# PDB_design.net
KiCad netlist of a schematic drawn in Altium Designer
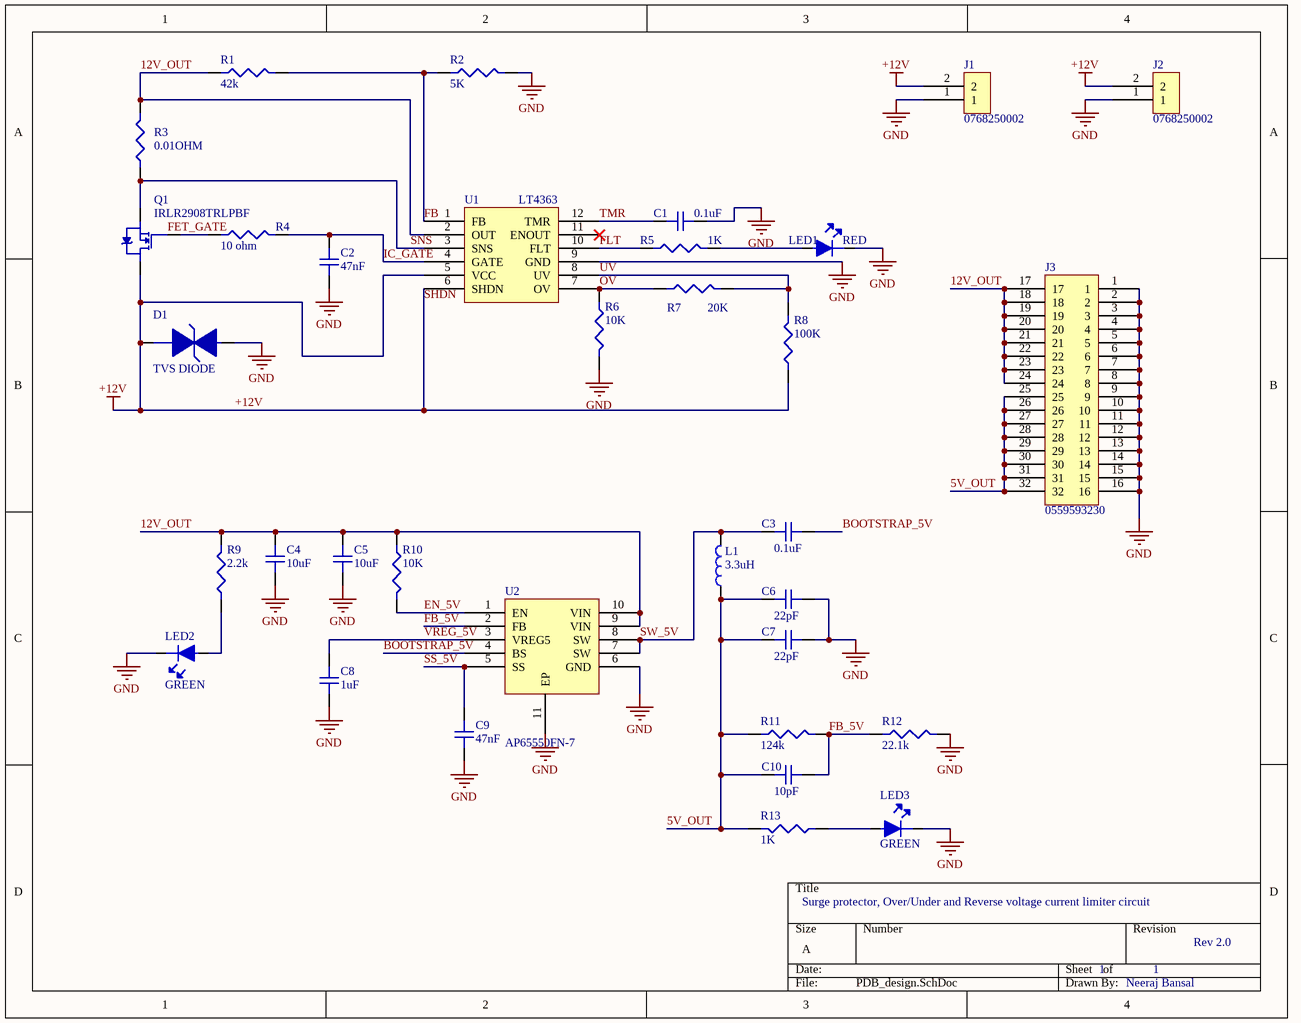
[diagram p0: PDB_design.SchDoc]

(export (version "E")
  (design (tool "Eeschema 10.0.6"))
  (components
    (comp (ref "C1")
      (value "0.1uF")
      (footprint "PDB:CAPC1613X09N")
      (description "0.1µF ±10% 25V Ceramic Capacitor X5R 0603 (1608 Metric)")
      (fields
        (field (name "MANUFACTURER") "Murata")
        (field (name "MANUFACTURER PART NUMBER") "GCM188R71H473KA55D")
      )
      (libsource (lib "PDB") (part "CL10A104KA8NNNC"))
    )
    (comp (ref "C2")
      (value "47nF")
      (footprint "PDB:CAPC1613X09N")
      (description "CAP CER 0.047UF 50V X7R 0603")
      (fields
        (field (name "MANUFACTURER") "Murata")
        (field (name "MANUFACTURER PART NUMBER") "GCM188R71H473KA55D")
      )
      (libsource (lib "PDB") (part "GCM188R71H473KA55D"))
    )
    (comp (ref "C3")
      (value "0.1uF")
      (footprint "PDB:CAPC1613X09N")
      (description "0.1µF ±10% 25V Ceramic Capacitor X5R 0603 (1608 Metric)")
      (fields
        (field (name "MANUFACTURER") "Murata")
        (field (name "MANUFACTURER PART NUMBER") "GCM188R71H473KA55D")
      )
      (libsource (lib "PDB") (part "CL10A104KA8NNNC"))
    )
    (comp (ref "C4")
      (value "10uF")
      (footprint "PDB:CAPC1613X09N")
      (description "10µF ±10% 10V Ceramic Capacitor X7R 0805 (2012 Metric)")
      (fields
        (field (name "MANUFACTURER") "Murata")
        (field (name "MANUFACTURER PART NUMBER") "GCM188R71H473KA55D")
      )
      (libsource (lib "PDB") (part "GRM21BR71A106KA73L"))
    )
    (comp (ref "C5")
      (value "10uF")
      (footprint "PDB:CAPC1613X09N")
      (description "10µF ±10% 10V Ceramic Capacitor X7R 0805 (2012 Metric)")
      (fields
        (field (name "MANUFACTURER") "Murata")
        (field (name "MANUFACTURER PART NUMBER") "GCM188R71H473KA55D")
      )
      (libsource (lib "PDB") (part "GRM21BR71A106KA73L"))
    )
    (comp (ref "C6")
      (value "22pF")
      (footprint "PDB:CAPC1613X09N")
      (description "22µF ±10% 10V Ceramic Capacitor X7R 1206 (3216 Metric)")
      (fields
        (field (name "MANUFACTURER") "Murata")
        (field (name "MANUFACTURER PART NUMBER") "GCM188R71H473KA55D")
      )
      (libsource (lib "PDB") (part "CL31B226KPHNNNE"))
    )
    (comp (ref "C7")
      (value "22pF")
      (footprint "PDB:CAPC1613X09N")
      (description "22µF ±10% 10V Ceramic Capacitor X7R 1206 (3216 Metric)")
      (fields
        (field (name "MANUFACTURER") "Murata")
        (field (name "MANUFACTURER PART NUMBER") "GCM188R71H473KA55D")
      )
      (libsource (lib "PDB") (part "CL31B226KPHNNNE"))
    )
    (comp (ref "C8")
      (value "1uF")
      (footprint "PDB:CAPC1613X09N")
      (description "1µF ±10% 50V Ceramic Capacitor X7R 0805 (2012 Metric)")
      (fields
        (field (name "MANUFACTURER") "Murata")
        (field (name "MANUFACTURER PART NUMBER") "GCM188R71H473KA55D")
      )
      (libsource (lib "PDB") (part "CL21B105KBFVPNE"))
    )
    (comp (ref "C9")
      (value "47nF")
      (footprint "PDB:CAPC1613X09N")
      (description "CAP CER 0.047UF 50V X7R 0603")
      (fields
        (field (name "MANUFACTURER") "Murata")
        (field (name "MANUFACTURER PART NUMBER") "GCM188R71H473KA55D")
      )
      (libsource (lib "PDB") (part "GCM188R71H473KA55D"))
    )
    (comp (ref "C10")
      (value "10pF")
      (footprint "PDB:CAPC1613X09N")
      (description "10pF ±10% 50V Ceramic Capacitor X7R 0805 (2012 Metric)")
      (fields
        (field (name "MANUFACTURER") "Murata")
        (field (name "MANUFACTURER PART NUMBER") "GCM188R71H473KA55D")
      )
      (libsource (lib "PDB") (part "C0805C100K5RAC7800"))
    )
    (comp (ref "D1")
      (value "TVS DIODE")
      (footprint "PDB:DIODE_TVS")
      (description "TVS DIODE 58VWM 93.6VC SMA")
      (fields (field (name "MANUFACTURER") "Diodes") (field (name "MANUFACTURER PART NUMBER") "SMAJ58A-13-F"))
      (libsource (lib "PDB") (part "SMAJ58A-13-F"))
    )
    (comp (ref "J1")
      (value "0768250002")
      (footprint "PDB:MOLEX_2PIN_MEGAFIT")
      (description "CONN_2Position_MEGAFIT Molex Through Hole, Right Angle Tin")
      (fields (field (name "MANUFACTURER") "Molex"))
      (libsource (lib "PDB") (part "0768250002"))
    )
    (comp (ref "J2")
      (value "0768250002")
      (footprint "PDB:MOLEX_2PIN_MEGAFIT")
      (description "CONN_2Position_MEGAFIT Molex Through Hole, Right Angle Tin")
      (fields (field (name "MANUFACTURER") "Molex"))
      (libsource (lib "PDB") (part "0768250002"))
    )
    (comp (ref "J3")
      (value "0559593230")
      (footprint "PDB_Components:MOLEX_32PIN")
      (libsource (lib "PDB") (part "0559593230"))
    )
    (comp (ref "L1")
      (value "3.3uH")
      (footprint "PDB:IND-6mm")
      (description "IND 3.3µH 6.5A 25.2 mOhm Max Nonstandard")
      (fields
        (field (name "MANUFACTURER") "Murata")
        (field (name "MANUFACTURER PART NUMBER") "1264EY-3R3N=P3")
      )
      (libsource (lib "PDB_symbols") (part "1264EY-3R3N=P3"))
    )
    (comp (ref "LED1")
      (value "RED")
      (footprint "PDB:LED")
      (description "Red  LED Indication - Discrete 2V 0603 (1608 Metric)")
      (fields
        (field (name "MANUFACTURER") "Wurth Electronics")
        (field (name "MANUFACTURER PART NUMBER") "150060VS75000")
      )
      (libsource (lib "PDB") (part "QTLP600CRTR"))
    )
    (comp (ref "LED2")
      (value "GREEN")
      (footprint "PDB:LED")
      (description "LED GREEN CLEAR 0603 SMD")
      (fields
        (field (name "MANUFACTURER") "Wurth Electronics")
        (field (name "MANUFACTURER PART NUMBER") "150060VS75000")
      )
      (libsource (lib "PDB") (part "150060VS75000"))
    )
    (comp (ref "LED3")
      (value "GREEN")
      (footprint "PDB:LED")
      (description "LED GREEN CLEAR 0603 SMD")
      (fields
        (field (name "MANUFACTURER") "Wurth Electronics")
        (field (name "MANUFACTURER PART NUMBER") "150060VS75000")
      )
      (libsource (lib "PDB") (part "150060VS75000"))
    )
    (comp (ref "Q1")
      (value "IRLR2908TRLPBF")
      (footprint "PDB:DPAK")
      (description "MOSFET N-CH 80V 30A DPAK")
      (fields (field (name "MANUFACTURER") "International Rectifier"))
      (libsource (lib "PDB") (part "IRLR2908TRLPBF"))
    )
    (comp (ref "R1")
      (value "42k")
      (footprint "PDB:R0805")
      (fields
        (field (name "MANUFACTURER") "Stackpole Electronics")
        (field (name "MANUFACTURER PART NUMBER") "RNCF0805DTE10K0")
        (field (name "TOLERANCE") "0.5%")
      )
      (libsource (lib "PDB") (part "RNCF0805DTE10K0_2_2"))
    )
    (comp (ref "R2")
      (value "5K")
      (footprint "PDB:R0805")
      (fields
        (field (name "MANUFACTURER") "Vishay Dale Thin Film")
        (field (name "MANUFACTURER PART NUMBER") "PNM0805E5001BST5")
        (field (name "TOLERANCE") "0.1%")
      )
      (libsource (lib "PDB") (part "PNM0805E5001BST5"))
    )
    (comp (ref "R3")
      (value "0.01OHM")
      (footprint "PDB:R2512")
      (description "RES SMD 0.01 OHM 1% 2W 2512")
      (fields
        (field (name "MANUFACTURER") "Yageo")
        (field (name "MANUFACTURER PART NUMBER") "PE2512FKE7W0R01L")
      )
      (libsource (lib "PDB") (part "PE2512FKE7W0R01L"))
    )
    (comp (ref "R4")
      (value "10 ohm")
      (footprint "PDB:R0805")
      (description "RES SMD 10 OHM 1% 1/3W 0805")
      (fields
        (field (name "MANUFACTURER") "Susumu")
        (field (name "MANUFACTURER PART NUMBER") "RL1220S-100-F")
      )
      (libsource (lib "PDB") (part "RL1220S-100-F"))
    )
    (comp (ref "R5")
      (value "1K")
      (footprint "PDB:R0805")
      (description "1 kOhms ±0.5% 0.125W, 1/8W Chip Resistor 0805 (2012 Metric) Automotive AEC-Q200 Thin Film")
      (fields
        (field (name "MANUFACTURER") "Stackpole Electronics")
        (field (name "MANUFACTURER PART NUMBER") "RNCF0805DTE10K0")
      )
      (libsource (lib "PDB") (part "RNCF0805DTE1K00"))
    )
    (comp (ref "R6")
      (value "10K")
      (footprint "PDB:R0805")
      (description "Res Thin Film 0805 10K Ohm 0.5% 0.1W(1/10W) ±25ppm/C Molded SMD Paper T/R")
      (fields
        (field (name "MANUFACTURER") "Stackpole Electronics")
        (field (name "MANUFACTURER PART NUMBER") "RNCF0805DTE10K0")
      )
      (libsource (lib "PDB") (part "RNCF0805DTE10K0"))
    )
    (comp (ref "R7")
      (value "20K")
      (footprint "PDB:R0805")
      (description "20 kOhms ±0.5% 0.125W, 1/8W Chip Resistor 0805 (2012 Metric) Automotive AEC-Q200 Thin Film")
      (fields
        (field (name "MANUFACTURER") "Stackpole Electronics")
        (field (name "MANUFACTURER PART NUMBER") "RNCF0805DTE10K0")
      )
      (libsource (lib "PDB") (part "RNCF0805DTE20K0"))
    )
    (comp (ref "R8")
      (value "100K")
      (footprint "PDB:R0805")
      (description "Res Thin Film 0805 100K Ohm 0.1% 0.125W(1/8W) ±25ppm/C Molded SMD Automotive Punched T/R")
      (fields
        (field (name "MANUFACTURER") "Panasonic")
        (field (name "MANUFACTURER PART NUMBER") "ERA-6AEB104V")
      )
      (libsource (lib "PDB") (part "ERA-6AEB104V"))
    )
    (comp (ref "R9")
      (value "2.2k")
      (footprint "PDB:R0805")
      (description "2.2 kOhms ±1% 0.125W, 1/8W Chip Resistor 0805 (2012 Metric) Moisture Resistant Thick Film")
      (fields
        (field (name "MANUFACTURER") "Stackpole Electronics")
        (field (name "MANUFACTURER PART NUMBER") "RNCF0805DTE10K0")
      )
      (libsource (lib "PDB") (part "RC0805FR-072K2L"))
    )
    (comp (ref "R10")
      (value "10K")
      (footprint "PDB:R0805")
      (description "Res Thin Film 0805 10K Ohm 0.5% 0.1W(1/10W) ±25ppm/C Molded SMD Paper T/R")
      (fields
        (field (name "MANUFACTURER") "Stackpole Electronics")
        (field (name "MANUFACTURER PART NUMBER") "RNCF0805DTE10K0")
      )
      (libsource (lib "PDB") (part "RNCF0805DTE10K0"))
    )
    (comp (ref "R11")
      (value "124k")
      (footprint "PDB:R0805")
      (description "124 kOhms ±0.1% 0.125W, 1/8W Chip Resistor 0805 (2012 Metric) Automotive AEC-Q200 Thin Film")
      (fields
        (field (name "MANUFACTURER") "Stackpole Electronics")
        (field (name "MANUFACTURER PART NUMBER") "RNCF0805DTE10K0")
      )
      (libsource (lib "PDB") (part "ERA-6AEB1243V"))
    )
    (comp (ref "R12")
      (value "22.1k")
      (footprint "PDB:R0805")
      (description "22.1 kOhms ±0.5% 0.125W, 1/8W Chip Resistor 0805 (2012 Metric) Automotive AEC-Q200 Thin Film")
      (fields
        (field (name "MANUFACTURER") "Stackpole Electronics")
        (field (name "MANUFACTURER PART NUMBER") "RNCF0805DTE10K0")
      )
      (libsource (lib "PDB") (part "RNCF0805DTE22K1"))
    )
    (comp (ref "R13")
      (value "1K")
      (footprint "PDB:R0805")
      (description "1 kOhms ±0.5% 0.125W, 1/8W Chip Resistor 0805 (2012 Metric) Automotive AEC-Q200 Thin Film")
      (fields
        (field (name "MANUFACTURER") "Stackpole Electronics")
        (field (name "MANUFACTURER PART NUMBER") "RNCF0805DTE10K0")
      )
      (libsource (lib "PDB") (part "RNCF0805DTE1K00"))
    )
    (comp (ref "U1")
      (value "LT4363")
      (footprint "PDB:TSOP65P490X110-12N")
      (description "IC SURGE STOPPER HV 12-MSOP")
      (fields
        (field (name "MANUFACTURER") "Analog Devices / Linear Technology")
        (field (name "MANUFACTURER PART NUMBER") "LT4363CMS-2#PBF")
      )
      (libsource (lib "PDB") (part "LT4363CMS-2#PBF"))
    )
    (comp (ref "U2")
      (value "AP65550FN-7")
      (footprint "PDB:DFN-10")
      (description "IC BUCK SYNC 5A, 18V VIN MAX 650kHz COT Step-Down Conv")
      (fields (field (name "MANUFACTURER") "Diodes"))
      (libsource (lib "PDB_symbols") (part "AP65550FN-7"))
    )
  )
  (nets
    (net (code "1") (name "+12V") (class "Default")
      (node (ref "D1") (pin "2") (pinfunction "2_2") (pintype "passive"))
      (node (ref "J1") (pin "2") (pinfunction "2_2") (pintype "passive"))
      (node (ref "J2") (pin "2") (pinfunction "2_2") (pintype "passive"))
      (node (ref "Q1") (pin "4") (pinfunction "4_4") (pintype "passive"))
      (node (ref "R8") (pin "1") (pinfunction "1_1") (pintype "passive"))
      (node (ref "U1") (pin "5") (pinfunction "VCC_5") (pintype "passive"))
      (node (ref "U1") (pin "6") (pinfunction "SHDN_6") (pintype "passive"))
    )
    (net (code "2") (name "/5V_OUT") (class "Default")
      (node (ref "C10") (pin "1") (pinfunction "1_1") (pintype "passive"))
      (node (ref "C6") (pin "1") (pinfunction "1_1") (pintype "passive"))
      (node (ref "C7") (pin "1") (pinfunction "1_1") (pintype "passive"))
      (node (ref "J3") (pin "25") (pinfunction "25_25") (pintype "passive"))
      (node (ref "J3") (pin "26") (pinfunction "26_26") (pintype "passive"))
      (node (ref "J3") (pin "27") (pinfunction "27_27") (pintype "passive"))
      (node (ref "J3") (pin "28") (pinfunction "28_28") (pintype "passive"))
      (node (ref "J3") (pin "29") (pinfunction "29_29") (pintype "passive"))
      (node (ref "J3") (pin "30") (pinfunction "30_30") (pintype "passive"))
      (node (ref "J3") (pin "31") (pinfunction "31_31") (pintype "passive"))
      (node (ref "J3") (pin "32") (pinfunction "32_32") (pintype "passive"))
      (node (ref "L1") (pin "1") (pinfunction "1_1") (pintype "passive"))
      (node (ref "R11") (pin "1") (pinfunction "1_1") (pintype "passive"))
      (node (ref "R13") (pin "2") (pinfunction "2_2") (pintype "passive"))
    )
    (net (code "3") (name "/12V_OUT") (class "Default")
      (node (ref "C4") (pin "2") (pinfunction "2_2") (pintype "passive"))
      (node (ref "C5") (pin "2") (pinfunction "2_2") (pintype "passive"))
      (node (ref "J3") (pin "17") (pinfunction "17_17") (pintype "passive"))
      (node (ref "J3") (pin "18") (pinfunction "18_18") (pintype "passive"))
      (node (ref "J3") (pin "19") (pinfunction "19_19") (pintype "passive"))
      (node (ref "J3") (pin "20") (pinfunction "20_20") (pintype "passive"))
      (node (ref "J3") (pin "21") (pinfunction "21_21") (pintype "passive"))
      (node (ref "J3") (pin "22") (pinfunction "22_22") (pintype "passive"))
      (node (ref "J3") (pin "23") (pinfunction "23_23") (pintype "passive"))
      (node (ref "J3") (pin "24") (pinfunction "24_24") (pintype "passive"))
      (node (ref "R1") (pin "1") (pinfunction "1_1") (pintype "passive"))
      (node (ref "R10") (pin "1") (pinfunction "1_1") (pintype "passive"))
      (node (ref "R3") (pin "2") (pinfunction "2_2") (pintype "passive"))
      (node (ref "R9") (pin "2") (pinfunction "2_2") (pintype "passive"))
      (node (ref "U1") (pin "2") (pinfunction "OUT_2") (pintype "passive"))
      (node (ref "U2") (pin "10") (pinfunction "VIN_10") (pintype "passive"))
      (node (ref "U2") (pin "9") (pinfunction "VIN_9") (pintype "passive"))
    )
    (net (code "4") (name "/BOOTSTRAP_5V") (class "Default")
      (node (ref "C3") (pin "2") (pinfunction "2_2") (pintype "passive"))
      (node (ref "U2") (pin "4") (pinfunction "BS_4") (pintype "passive"))
    )
    (net (code "5") (name "/EN_5V") (class "Default")
      (node (ref "R10") (pin "2") (pinfunction "2_2") (pintype "passive"))
      (node (ref "U2") (pin "1") (pinfunction "EN_1") (pintype "passive"))
    )
    (net (code "6") (name "/FB") (class "Default")
      (node (ref "R1") (pin "2") (pinfunction "2_2") (pintype "passive"))
      (node (ref "R2") (pin "1") (pinfunction "1_1") (pintype "passive"))
      (node (ref "U1") (pin "1") (pinfunction "FB_1") (pintype "passive"))
    )
    (net (code "7") (name "/FB_5V") (class "Default")
      (node (ref "C10") (pin "2") (pinfunction "2_2") (pintype "passive"))
      (node (ref "R11") (pin "2") (pinfunction "2_2") (pintype "passive"))
      (node (ref "R12") (pin "1") (pinfunction "1_1") (pintype "passive"))
      (node (ref "U2") (pin "2") (pinfunction "FB_2") (pintype "passive"))
    )
    (net (code "9") (name "/FLT") (class "Default")
      (node (ref "R5") (pin "1") (pinfunction "1_1") (pintype "passive"))
      (node (ref "U1") (pin "10") (pinfunction "FLT_10") (pintype "passive"))
    )
    (net (code "10") (name "/IC_GATE") (class "Default")
      (node (ref "C2") (pin "2") (pinfunction "2_2") (pintype "passive"))
      (node (ref "R4") (pin "2") (pinfunction "2_2") (pintype "passive"))
      (node (ref "U1") (pin "4") (pinfunction "GATE_4") (pintype "passive"))
    )
    (net (code "11") (name "/OV") (class "Default")
      (node (ref "R6") (pin "1") (pinfunction "1_1") (pintype "passive"))
      (node (ref "R7") (pin "1") (pinfunction "1_1") (pintype "passive"))
      (node (ref "U1") (pin "7") (pinfunction "OV_7") (pintype "passive"))
    )
    (net (code "12") (name "/SNS") (class "Default")
      (node (ref "Q1") (pin "3") (pinfunction "3_3") (pintype "passive"))
      (node (ref "R3") (pin "1") (pinfunction "1_1") (pintype "passive"))
      (node (ref "U1") (pin "3") (pinfunction "SNS_3") (pintype "passive"))
    )
    (net (code "13") (name "/SS_5V") (class "Default")
      (node (ref "C9") (pin "2") (pinfunction "2_2") (pintype "passive"))
      (node (ref "U2") (pin "5") (pinfunction "SS_5") (pintype "passive"))
    )
    (net (code "14") (name "/SW_5V") (class "Default")
      (node (ref "C3") (pin "1") (pinfunction "1_1") (pintype "passive"))
      (node (ref "L1") (pin "2") (pinfunction "2_2") (pintype "passive"))
      (node (ref "U2") (pin "7") (pinfunction "SW_7") (pintype "passive"))
      (node (ref "U2") (pin "8") (pinfunction "SW_8") (pintype "passive"))
    )
    (net (code "15") (name "/TMR") (class "Default")
      (node (ref "C1") (pin "1") (pinfunction "1_1") (pintype "passive"))
      (node (ref "U1") (pin "12") (pinfunction "TMR_12") (pintype "passive"))
    )
    (net (code "16") (name "/UV") (class "Default")
      (node (ref "R7") (pin "2") (pinfunction "2_2") (pintype "passive"))
      (node (ref "R8") (pin "2") (pinfunction "2_2") (pintype "passive"))
      (node (ref "U1") (pin "8") (pinfunction "UV_8") (pintype "passive"))
    )
    (net (code "17") (name "/VREG_5V") (class "Default")
      (node (ref "C8") (pin "2") (pinfunction "2_2") (pintype "passive"))
      (node (ref "U2") (pin "3") (pinfunction "VREG5_3") (pintype "passive"))
    )
    (net (code "18") (name "GND") (class "Default")
      (node (ref "C1") (pin "2") (pinfunction "2_2") (pintype "passive"))
      (node (ref "C2") (pin "1") (pinfunction "1_1") (pintype "passive"))
      (node (ref "C4") (pin "1") (pinfunction "1_1") (pintype "passive"))
      (node (ref "C5") (pin "1") (pinfunction "1_1") (pintype "passive"))
      (node (ref "C6") (pin "2") (pinfunction "2_2") (pintype "passive"))
      (node (ref "C7") (pin "2") (pinfunction "2_2") (pintype "passive"))
      (node (ref "C8") (pin "1") (pinfunction "1_1") (pintype "passive"))
      (node (ref "C9") (pin "1") (pinfunction "1_1") (pintype "passive"))
      (node (ref "D1") (pin "1") (pinfunction "1_1") (pintype "passive"))
      (node (ref "J1") (pin "1") (pinfunction "1_1") (pintype "passive"))
      (node (ref "J2") (pin "1") (pinfunction "1_1") (pintype "passive"))
      (node (ref "J3") (pin "1") (pinfunction "1_1") (pintype "passive"))
      (node (ref "J3") (pin "10") (pinfunction "10_10") (pintype "passive"))
      (node (ref "J3") (pin "11") (pinfunction "11_11") (pintype "passive"))
      (node (ref "J3") (pin "12") (pinfunction "12_12") (pintype "passive"))
      (node (ref "J3") (pin "13") (pinfunction "13_13") (pintype "passive"))
      (node (ref "J3") (pin "14") (pinfunction "14_14") (pintype "passive"))
      (node (ref "J3") (pin "15") (pinfunction "15_15") (pintype "passive"))
      (node (ref "J3") (pin "16") (pinfunction "16_16") (pintype "passive"))
      (node (ref "J3") (pin "2") (pinfunction "2_2") (pintype "passive"))
      (node (ref "J3") (pin "3") (pinfunction "3_3") (pintype "passive"))
      (node (ref "J3") (pin "4") (pinfunction "4_4") (pintype "passive"))
      (node (ref "J3") (pin "5") (pinfunction "5_5") (pintype "passive"))
      (node (ref "J3") (pin "6") (pinfunction "6_6") (pintype "passive"))
      (node (ref "J3") (pin "7") (pinfunction "7_7") (pintype "passive"))
      (node (ref "J3") (pin "8") (pinfunction "8_8") (pintype "passive"))
      (node (ref "J3") (pin "9") (pinfunction "9_9") (pintype "passive"))
      (node (ref "LED1") (pin "2") (pinfunction "2_2") (pintype "passive"))
      (node (ref "LED2") (pin "2") (pinfunction "2_2") (pintype "passive"))
      (node (ref "LED3") (pin "2") (pinfunction "2_2") (pintype "passive"))
      (node (ref "R12") (pin "2") (pinfunction "2_2") (pintype "passive"))
      (node (ref "R2") (pin "2") (pinfunction "2_2") (pintype "passive"))
      (node (ref "R6") (pin "2") (pinfunction "2_2") (pintype "passive"))
      (node (ref "U1") (pin "9") (pinfunction "GND_9") (pintype "passive"))
      (node (ref "U2") (pin "11") (pinfunction "EP_11") (pintype "passive"))
      (node (ref "U2") (pin "6") (pinfunction "GND_6") (pintype "passive"))
    )
    (net (code "19") (name "Net-(LED1-Pad1)") (class "Default")
      (node (ref "LED1") (pin "1") (pinfunction "1_1") (pintype "passive"))
      (node (ref "R5") (pin "2") (pinfunction "2_2") (pintype "passive"))
    )
    (net (code "20") (name "Net-(LED2-Pad1)") (class "Default")
      (node (ref "LED2") (pin "1") (pinfunction "1_1") (pintype "passive"))
      (node (ref "R9") (pin "1") (pinfunction "1_1") (pintype "passive"))
    )
    (net (code "21") (name "Net-(LED3-Pad1)") (class "Default")
      (node (ref "LED3") (pin "1") (pinfunction "1_1") (pintype "passive"))
      (node (ref "R13") (pin "1") (pinfunction "1_1") (pintype "passive"))
    )
    (net (code "22") (name "Net-(Q1-Pad1)") (class "Default")
      (node (ref "Q1") (pin "1") (pinfunction "1_1") (pintype "passive"))
      (node (ref "R4") (pin "1") (pinfunction "1_1") (pintype "passive"))
    )
    (net (code "23") (name "unconnected-(U1-ENOUT-Pad11)") (class "Default")
      (node (ref "U1") (pin "11") (pinfunction "ENOUT_11") (pintype "passive+no_connect"))
    )
  )
)
